# syscharge.net
KiCad netlist of a schematic drawn in EAGLE
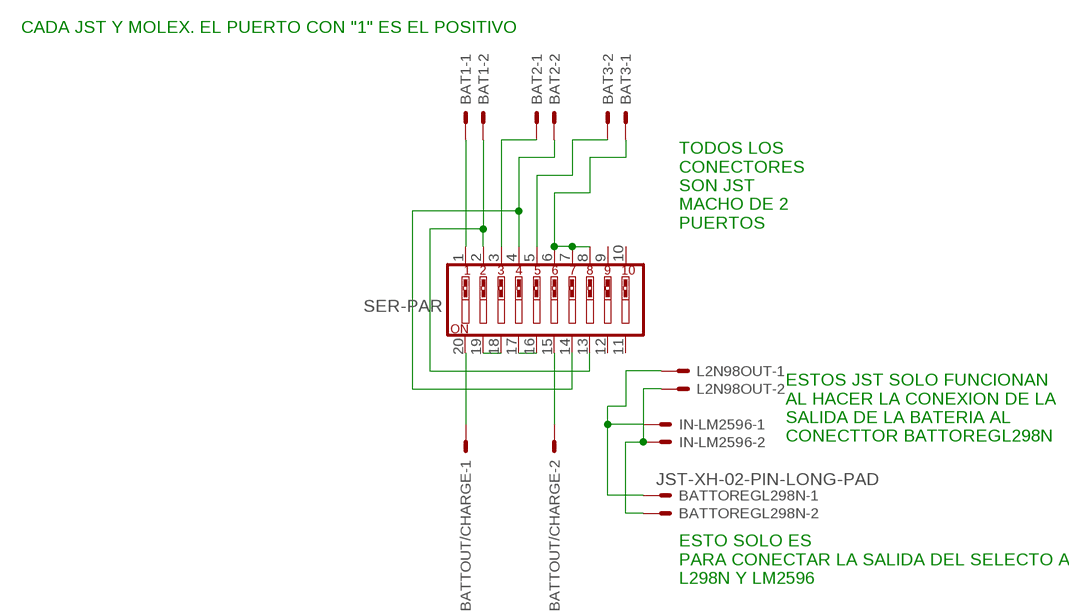
[diagram p0: schematic, sheet 1]

(export (version "E")
  (design (tool "Eeschema 10.0.6"))
  (components
    (comp (ref "BAT1")
      (value "JST-XH-02-PIN-LONG-PAD")
      (footprint "eagle-import:JST-XH-02-PACKAGE-LONG-PAD")
      (libsource (lib "eagle-import") (part "JST-XH-02-PIN-LONG-PAD"))
    )
    (comp (ref "BAT2")
      (value "JST-XH-02-PIN-LONG-PAD")
      (footprint "eagle-import:JST-XH-02-PACKAGE-LONG-PAD")
      (libsource (lib "eagle-import") (part "JST-XH-02-PIN-LONG-PAD"))
    )
    (comp (ref "BAT3")
      (value "JST-XH-02-PIN-LONG-PAD")
      (footprint "eagle-import:JST-XH-02-PACKAGE-LONG-PAD")
      (libsource (lib "eagle-import") (part "JST-XH-02-PIN-LONG-PAD"))
    )
    (comp (ref "BATTOREGL298N")
      (value "JST-XH-02-PIN-LONG-PAD")
      (footprint "eagle-import:JST-XH-02-PACKAGE-LONG-PAD")
      (libsource (lib "eagle-import") (part "JST-XH-02-PIN-LONG-PAD"))
    )
    (comp (ref "BATTOUT/CHARGE")
      (value "JST-XH-02-PIN-LONG-PAD")
      (footprint "eagle-import:JST-XH-02-PACKAGE-LONG-PAD")
      (libsource (lib "eagle-import") (part "JST-XH-02-PIN-LONG-PAD"))
    )
    (comp (ref "IN-LM2596")
      (value "JST-XH-02-PIN-LONG-PAD")
      (footprint "eagle-import:JST-XH-02-PACKAGE-LONG-PAD")
      (libsource (lib "eagle-import") (part "JST-XH-02-PIN-LONG-PAD"))
    )
    (comp (ref "L2N98OUT")
      (value "JST-XH-02-PIN-LONG-PAD")
      (footprint "eagle-import:JST-XH-02-PACKAGE-LONG-PAD")
      (libsource (lib "eagle-import") (part "JST-XH-02-PIN-LONG-PAD"))
    )
    (comp (ref "SER-PAR")
      (value "SW_DIP-10")
      (footprint "eagle-import:EDG-10")
      (libsource (lib "eagle-import") (part "SW_DIP-10"))
    )
  )
  (nets
    (net (code "1") (name "Net-(BAT1A-S)") (class "Default")
      (node (ref "BAT1") (pin "1") (pinfunction "S_1") (pintype "passive"))
      (node (ref "SER-PAR") (pin "1") (pinfunction "1_1") (pintype "passive"))
    )
    (net (code "2") (name "Net-(BAT1B-S)") (class "Default")
      (node (ref "BAT1") (pin "2") (pinfunction "S_2") (pintype "passive"))
      (node (ref "SER-PAR") (pin "13") (pinfunction "13_13") (pintype "passive"))
      (node (ref "SER-PAR") (pin "2") (pinfunction "2_2") (pintype "passive"))
    )
    (net (code "3") (name "Net-(BAT2A-S)") (class "Default")
      (node (ref "BAT2") (pin "1") (pinfunction "S_1") (pintype "passive"))
      (node (ref "SER-PAR") (pin "3") (pinfunction "3_3") (pintype "passive"))
    )
    (net (code "4") (name "Net-(BAT2B-S)") (class "Default")
      (node (ref "BAT2") (pin "2") (pinfunction "S_2") (pintype "passive"))
      (node (ref "SER-PAR") (pin "14") (pinfunction "14_14") (pintype "passive"))
      (node (ref "SER-PAR") (pin "4") (pinfunction "4_4") (pintype "passive"))
    )
    (net (code "5") (name "Net-(BAT3A-S)") (class "Default")
      (node (ref "BAT3") (pin "1") (pinfunction "S_1") (pintype "passive"))
      (node (ref "SER-PAR") (pin "6") (pinfunction "6_6") (pintype "passive"))
      (node (ref "SER-PAR") (pin "7") (pinfunction "7_7") (pintype "passive"))
      (node (ref "SER-PAR") (pin "8") (pinfunction "8_8") (pintype "passive"))
    )
    (net (code "6") (name "Net-(BAT3B-S)") (class "Default")
      (node (ref "BAT3") (pin "2") (pinfunction "S_2") (pintype "passive"))
      (node (ref "SER-PAR") (pin "5") (pinfunction "5_5") (pintype "passive"))
    )
    (net (code "7") (name "Net-(BATTOREGL298NA-S)") (class "Default")
      (node (ref "BATTOREGL298N") (pin "1") (pinfunction "S_1") (pintype "passive"))
      (node (ref "IN-LM2596") (pin "1") (pinfunction "S_1") (pintype "passive"))
      (node (ref "L2N98OUT") (pin "1") (pinfunction "S_1") (pintype "passive"))
    )
    (net (code "8") (name "Net-(BATTOREGL298NB-S)") (class "Default")
      (node (ref "BATTOREGL298N") (pin "2") (pinfunction "S_2") (pintype "passive"))
      (node (ref "IN-LM2596") (pin "2") (pinfunction "S_2") (pintype "passive"))
      (node (ref "L2N98OUT") (pin "2") (pinfunction "S_2") (pintype "passive"))
    )
    (net (code "9") (name "Net-(BATTOUT/CHARGEA-S)") (class "Default")
      (node (ref "BATTOUT/CHARGE") (pin "1") (pinfunction "S_1") (pintype "passive"))
      (node (ref "SER-PAR") (pin "20") (pinfunction "20_20") (pintype "passive"))
    )
    (net (code "10") (name "Net-(BATTOUT/CHARGEB-S)") (class "Default")
      (node (ref "BATTOUT/CHARGE") (pin "2") (pinfunction "S_2") (pintype "passive"))
      (node (ref "SER-PAR") (pin "15") (pinfunction "15_15") (pintype "passive"))
    )
    (net (code "11") (name "Net-(SER-PAR-Pad16)") (class "Default")
      (node (ref "SER-PAR") (pin "16") (pinfunction "16_16") (pintype "passive"))
      (node (ref "SER-PAR") (pin "17") (pinfunction "17_17") (pintype "passive"))
    )
    (net (code "12") (name "Net-(SER-PAR-Pad18)") (class "Default")
      (node (ref "SER-PAR") (pin "18") (pinfunction "18_18") (pintype "passive"))
      (node (ref "SER-PAR") (pin "19") (pinfunction "19_19") (pintype "passive"))
    )
    (net (code "13") (name "unconnected-(SER-PAR-Pad9)") (class "Default")
      (node (ref "SER-PAR") (pin "9") (pinfunction "9_9") (pintype "passive"))
    )
    (net (code "14") (name "unconnected-(SER-PAR-Pad10)") (class "Default")
      (node (ref "SER-PAR") (pin "10") (pinfunction "10_10") (pintype "passive"))
    )
    (net (code "15") (name "unconnected-(SER-PAR-Pad11)") (class "Default")
      (node (ref "SER-PAR") (pin "11") (pinfunction "11_11") (pintype "passive"))
    )
    (net (code "16") (name "unconnected-(SER-PAR-Pad12)") (class "Default")
      (node (ref "SER-PAR") (pin "12") (pinfunction "12_12") (pintype "passive"))
    )
  )
)
